# Alimentation.net
KiCad netlist of a schematic drawn in Altium Designer
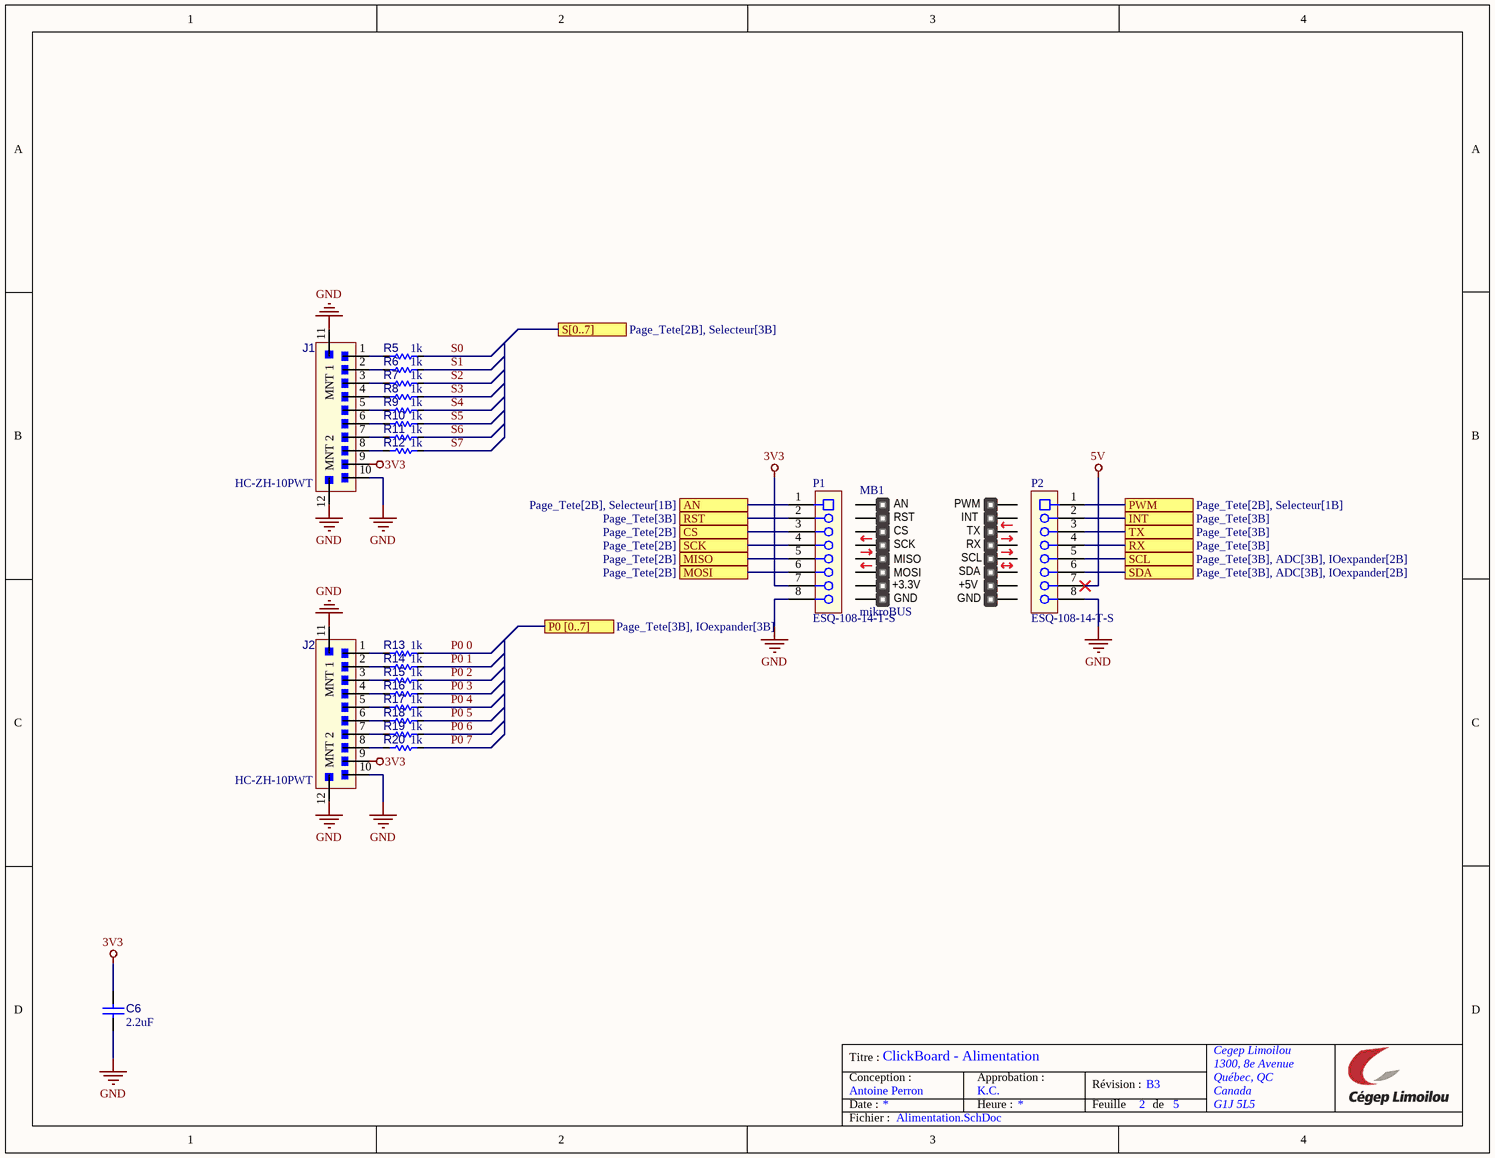
[diagram p0: Alimentation.SchDoc]

(export (version "E")
  (design (tool "Eeschema 10.0.6"))
  (components
    (comp (ref "C6")
      (value "2.2uF")
      (footprint "C_1608[0603]")
      (description "Capacitor type 1")
      (fields (field (name "TOLERANCE") "10%") (field (name "Comment") "CAP CER 2.2uF 10V X7R 0603"))
      (libsource (lib "TEP-AltiumLib-Passives-RLC") (part "capacitor"))
    )
    (comp (ref "J1")
      (value "HC-ZH-10PWT")
      (footprint "J_S10B-ZR-SM4")
      (description "CONN wire to board SMT R/A 10POS 1.5mm")
      (libsource (lib "TEP-AltiumLib-Connectors") (part "CONN-1MM5-01X10-S10B-H-SMT"))
    )
    (comp (ref "J2")
      (value "HC-ZH-10PWT")
      (footprint "J_S10B-ZR-SM4")
      (description "CONN wire to board SMT R/A 10POS 1.5mm")
      (libsource (lib "TEP-AltiumLib-Connectors") (part "CONN-1MM5-01X10-S10B-H-SMT"))
    )
    (comp (ref "MB1")
      (value "mikroBUS")
      (footprint "mikroBUS-Large-No-Connector")
      (description "mikroBUS compatible add-on board")
      (libsource (lib "TEP-AltiumLib-Modules") (part "mikroBUS compatible add-on board"))
    )
    (comp (ref "P1")
      (value "ESQ-108-14-T-S")
      (footprint "CONN_SKT_01X08_100MIL-ELEVATED-LONGPIN")
      (description "CONN SOCKET 8pos 100mils Elevated")
      (libsource (lib "TEP-AltiumLib-Connectors") (part "CONN-100MIL-SKT-01X08_ELEVATED_LONGPIN"))
    )
    (comp (ref "P2")
      (value "ESQ-108-14-T-S")
      (footprint "CONN_SKT_01X08_100MIL-ELEVATED-LONGPIN")
      (description "CONN SOCKET 8pos 100mils Elevated")
      (libsource (lib "") (part "CONN-100MIL-SKT-01X08_ELEVATED_LONGPIN_1"))
    )
    (comp (ref "R5")
      (value "1k")
      (footprint "R_1608[0603]")
      (description "Resistor type 1")
      (fields (field (name "TOLERANCE") "1%") (field (name "Comment") "Res 1k 1% 0603"))
      (libsource (lib "TEP-AltiumLib-Passives-RLC") (part "resistor"))
    )
    (comp (ref "R6")
      (value "1k")
      (footprint "R_1608[0603]")
      (description "Resistor type 1")
      (fields (field (name "TOLERANCE") "1%") (field (name "Comment") "Res 1k 1% 0603"))
      (libsource (lib "TEP-AltiumLib-Passives-RLC") (part "resistor"))
    )
    (comp (ref "R7")
      (value "1k")
      (footprint "R_1608[0603]")
      (description "Resistor type 1")
      (fields (field (name "TOLERANCE") "1%") (field (name "Comment") "Res 1k 1% 0603"))
      (libsource (lib "TEP-AltiumLib-Passives-RLC") (part "resistor"))
    )
    (comp (ref "R8")
      (value "1k")
      (footprint "R_1608[0603]")
      (description "Resistor type 1")
      (fields (field (name "TOLERANCE") "1%") (field (name "Comment") "Res 1k 1% 0603"))
      (libsource (lib "TEP-AltiumLib-Passives-RLC") (part "resistor"))
    )
    (comp (ref "R9")
      (value "1k")
      (footprint "R_1608[0603]")
      (description "Resistor type 1")
      (fields (field (name "TOLERANCE") "1%") (field (name "Comment") "Res 1k 1% 0603"))
      (libsource (lib "TEP-AltiumLib-Passives-RLC") (part "resistor"))
    )
    (comp (ref "R10")
      (value "1k")
      (footprint "R_1608[0603]")
      (description "Resistor type 1")
      (fields (field (name "TOLERANCE") "1%") (field (name "Comment") "Res 1k 1% 0603"))
      (libsource (lib "TEP-AltiumLib-Passives-RLC") (part "resistor"))
    )
    (comp (ref "R11")
      (value "1k")
      (footprint "R_1608[0603]")
      (description "Resistor type 1")
      (fields (field (name "TOLERANCE") "1%") (field (name "Comment") "Res 1k 1% 0603"))
      (libsource (lib "TEP-AltiumLib-Passives-RLC") (part "resistor"))
    )
    (comp (ref "R12")
      (value "1k")
      (footprint "R_1608[0603]")
      (description "Resistor type 1")
      (fields (field (name "TOLERANCE") "1%") (field (name "Comment") "Res 1k 1% 0603"))
      (libsource (lib "TEP-AltiumLib-Passives-RLC") (part "resistor"))
    )
    (comp (ref "R13")
      (value "1k")
      (footprint "R_1608[0603]")
      (description "Resistor type 1")
      (fields (field (name "TOLERANCE") "1%") (field (name "Comment") "Res 1k 1% 0603"))
      (libsource (lib "TEP-AltiumLib-Passives-RLC") (part "resistor"))
    )
    (comp (ref "R14")
      (value "1k")
      (footprint "R_1608[0603]")
      (description "Resistor type 1")
      (fields (field (name "TOLERANCE") "1%") (field (name "Comment") "Res 1k 1% 0603"))
      (libsource (lib "TEP-AltiumLib-Passives-RLC") (part "resistor"))
    )
    (comp (ref "R15")
      (value "1k")
      (footprint "R_1608[0603]")
      (description "Resistor type 1")
      (fields (field (name "TOLERANCE") "1%") (field (name "Comment") "Res 1k 1% 0603"))
      (libsource (lib "TEP-AltiumLib-Passives-RLC") (part "resistor"))
    )
    (comp (ref "R16")
      (value "1k")
      (footprint "R_1608[0603]")
      (description "Resistor type 1")
      (fields (field (name "TOLERANCE") "1%") (field (name "Comment") "Res 1k 1% 0603"))
      (libsource (lib "TEP-AltiumLib-Passives-RLC") (part "resistor"))
    )
    (comp (ref "R17")
      (value "1k")
      (footprint "R_1608[0603]")
      (description "Resistor type 1")
      (fields (field (name "TOLERANCE") "1%") (field (name "Comment") "Res 1k 1% 0603"))
      (libsource (lib "TEP-AltiumLib-Passives-RLC") (part "resistor"))
    )
    (comp (ref "R18")
      (value "1k")
      (footprint "R_1608[0603]")
      (description "Resistor type 1")
      (fields (field (name "TOLERANCE") "1%") (field (name "Comment") "Res 1k 1% 0603"))
      (libsource (lib "TEP-AltiumLib-Passives-RLC") (part "resistor"))
    )
    (comp (ref "R19")
      (value "1k")
      (footprint "R_1608[0603]")
      (description "Resistor type 1")
      (fields (field (name "TOLERANCE") "1%") (field (name "Comment") "Res 1k 1% 0603"))
      (libsource (lib "TEP-AltiumLib-Passives-RLC") (part "resistor"))
    )
    (comp (ref "R20")
      (value "1k")
      (footprint "R_1608[0603]")
      (description "Resistor type 1")
      (fields (field (name "TOLERANCE") "1%") (field (name "Comment") "Res 1k 1% 0603"))
      (libsource (lib "TEP-AltiumLib-Passives-RLC") (part "resistor"))
    )
  )
  (nets
    (net (code "1") (name "/AN") (class "Default")
      (node (ref "P1") (pin "1") (pinfunction "1_1") (pintype "passive"))
    )
    (net (code "2") (name "/CS") (class "Default")
      (node (ref "P1") (pin "3") (pinfunction "3_3") (pintype "passive"))
    )
    (net (code "3") (name "/INT") (class "Default")
      (node (ref "P2") (pin "2") (pinfunction "2_2") (pintype "passive"))
    )
    (net (code "4") (name "/MISO") (class "Default")
      (node (ref "P1") (pin "5") (pinfunction "5_5") (pintype "passive"))
    )
    (net (code "5") (name "/MOSI") (class "Default")
      (node (ref "P1") (pin "6") (pinfunction "6_6") (pintype "passive"))
    )
    (net (code "6") (name "/P0 0") (class "Default")
      (node (ref "R13") (pin "2") (pinfunction "2_2") (pintype "passive"))
    )
    (net (code "7") (name "/P0 1") (class "Default")
      (node (ref "R14") (pin "2") (pinfunction "2_2") (pintype "passive"))
    )
    (net (code "8") (name "/P0 2") (class "Default")
      (node (ref "R15") (pin "2") (pinfunction "2_2") (pintype "passive"))
    )
    (net (code "9") (name "/P0 3") (class "Default")
      (node (ref "R16") (pin "2") (pinfunction "2_2") (pintype "passive"))
    )
    (net (code "10") (name "/P0 4") (class "Default")
      (node (ref "R17") (pin "2") (pinfunction "2_2") (pintype "passive"))
    )
    (net (code "11") (name "/P0 5") (class "Default")
      (node (ref "R18") (pin "2") (pinfunction "2_2") (pintype "passive"))
    )
    (net (code "12") (name "/P0 6") (class "Default")
      (node (ref "R19") (pin "2") (pinfunction "2_2") (pintype "passive"))
    )
    (net (code "13") (name "/P0 7") (class "Default")
      (node (ref "R20") (pin "2") (pinfunction "2_2") (pintype "passive"))
    )
    (net (code "15") (name "/PWM") (class "Default")
      (node (ref "P2") (pin "1") (pinfunction "1_1") (pintype "passive"))
    )
    (net (code "16") (name "/RST") (class "Default")
      (node (ref "P1") (pin "2") (pinfunction "2_2") (pintype "passive"))
    )
    (net (code "17") (name "/RX") (class "Default")
      (node (ref "P2") (pin "4") (pinfunction "4_4") (pintype "passive"))
    )
    (net (code "18") (name "/S0") (class "Default")
      (node (ref "R5") (pin "2") (pinfunction "2_2") (pintype "passive"))
    )
    (net (code "19") (name "/S1") (class "Default")
      (node (ref "R6") (pin "2") (pinfunction "2_2") (pintype "passive"))
    )
    (net (code "20") (name "/S2") (class "Default")
      (node (ref "R7") (pin "2") (pinfunction "2_2") (pintype "passive"))
    )
    (net (code "21") (name "/S3") (class "Default")
      (node (ref "R8") (pin "2") (pinfunction "2_2") (pintype "passive"))
    )
    (net (code "22") (name "/S4") (class "Default")
      (node (ref "R9") (pin "2") (pinfunction "2_2") (pintype "passive"))
    )
    (net (code "23") (name "/S5") (class "Default")
      (node (ref "R10") (pin "2") (pinfunction "2_2") (pintype "passive"))
    )
    (net (code "24") (name "/S6") (class "Default")
      (node (ref "R11") (pin "2") (pinfunction "2_2") (pintype "passive"))
    )
    (net (code "25") (name "/S7") (class "Default")
      (node (ref "R12") (pin "2") (pinfunction "2_2") (pintype "passive"))
    )
    (net (code "26") (name "/SCK") (class "Default")
      (node (ref "P1") (pin "4") (pinfunction "4_4") (pintype "passive"))
    )
    (net (code "27") (name "/SCL") (class "Default")
      (node (ref "P2") (pin "5") (pinfunction "5_5") (pintype "passive"))
    )
    (net (code "28") (name "/SDA") (class "Default")
      (node (ref "P2") (pin "6") (pinfunction "6_6") (pintype "passive"))
    )
    (net (code "30") (name "/TX") (class "Default")
      (node (ref "P2") (pin "3") (pinfunction "3_3") (pintype "passive"))
    )
    (net (code "31") (name "3V3") (class "Default")
      (node (ref "C6") (pin "2") (pinfunction "2_2") (pintype "passive"))
      (node (ref "J1") (pin "9") (pinfunction "9_9") (pintype "passive"))
      (node (ref "J2") (pin "9") (pinfunction "9_9") (pintype "passive"))
      (node (ref "P1") (pin "7") (pinfunction "7_7") (pintype "passive"))
    )
    (net (code "32") (name "5V") (class "Default")
      (node (ref "P2") (pin "7") (pinfunction "7_7") (pintype "passive"))
    )
    (net (code "33") (name "GND") (class "Default")
      (node (ref "C6") (pin "1") (pinfunction "1_1") (pintype "passive"))
      (node (ref "J1") (pin "10") (pinfunction "10_10") (pintype "passive"))
      (node (ref "J1") (pin "11") (pinfunction "MNT_1_11") (pintype "passive"))
      (node (ref "J1") (pin "12") (pinfunction "MNT_2_12") (pintype "passive"))
      (node (ref "J2") (pin "10") (pinfunction "10_10") (pintype "passive"))
      (node (ref "J2") (pin "11") (pinfunction "MNT_1_11") (pintype "passive"))
      (node (ref "J2") (pin "12") (pinfunction "MNT_2_12") (pintype "passive"))
      (node (ref "P1") (pin "8") (pinfunction "8_8") (pintype "passive"))
      (node (ref "P2") (pin "8") (pinfunction "8_8") (pintype "passive"))
    )
    (net (code "34") (name "Net-(J1-Pad1)") (class "Default")
      (node (ref "J1") (pin "1") (pinfunction "1_1") (pintype "passive"))
      (node (ref "R5") (pin "1") (pinfunction "1_1") (pintype "passive"))
    )
    (net (code "35") (name "Net-(J1-Pad2)") (class "Default")
      (node (ref "J1") (pin "2") (pinfunction "2_2") (pintype "passive"))
      (node (ref "R6") (pin "1") (pinfunction "1_1") (pintype "passive"))
    )
    (net (code "36") (name "Net-(J1-Pad3)") (class "Default")
      (node (ref "J1") (pin "3") (pinfunction "3_3") (pintype "passive"))
      (node (ref "R7") (pin "1") (pinfunction "1_1") (pintype "passive"))
    )
    (net (code "37") (name "Net-(J1-Pad4)") (class "Default")
      (node (ref "J1") (pin "4") (pinfunction "4_4") (pintype "passive"))
      (node (ref "R8") (pin "1") (pinfunction "1_1") (pintype "passive"))
    )
    (net (code "38") (name "Net-(J1-Pad5)") (class "Default")
      (node (ref "J1") (pin "5") (pinfunction "5_5") (pintype "passive"))
      (node (ref "R9") (pin "1") (pinfunction "1_1") (pintype "passive"))
    )
    (net (code "39") (name "Net-(J1-Pad6)") (class "Default")
      (node (ref "J1") (pin "6") (pinfunction "6_6") (pintype "passive"))
      (node (ref "R10") (pin "1") (pinfunction "1_1") (pintype "passive"))
    )
    (net (code "40") (name "Net-(J1-Pad7)") (class "Default")
      (node (ref "J1") (pin "7") (pinfunction "7_7") (pintype "passive"))
      (node (ref "R11") (pin "1") (pinfunction "1_1") (pintype "passive"))
    )
    (net (code "41") (name "Net-(J1-Pad8)") (class "Default")
      (node (ref "J1") (pin "8") (pinfunction "8_8") (pintype "passive"))
      (node (ref "R12") (pin "1") (pinfunction "1_1") (pintype "passive"))
    )
    (net (code "42") (name "Net-(J2-Pad1)") (class "Default")
      (node (ref "J2") (pin "1") (pinfunction "1_1") (pintype "passive"))
      (node (ref "R13") (pin "1") (pinfunction "1_1") (pintype "passive"))
    )
    (net (code "43") (name "Net-(J2-Pad2)") (class "Default")
      (node (ref "J2") (pin "2") (pinfunction "2_2") (pintype "passive"))
      (node (ref "R14") (pin "1") (pinfunction "1_1") (pintype "passive"))
    )
    (net (code "44") (name "Net-(J2-Pad3)") (class "Default")
      (node (ref "J2") (pin "3") (pinfunction "3_3") (pintype "passive"))
      (node (ref "R15") (pin "1") (pinfunction "1_1") (pintype "passive"))
    )
    (net (code "45") (name "Net-(J2-Pad4)") (class "Default")
      (node (ref "J2") (pin "4") (pinfunction "4_4") (pintype "passive"))
      (node (ref "R16") (pin "1") (pinfunction "1_1") (pintype "passive"))
    )
    (net (code "46") (name "Net-(J2-Pad5)") (class "Default")
      (node (ref "J2") (pin "5") (pinfunction "5_5") (pintype "passive"))
      (node (ref "R17") (pin "1") (pinfunction "1_1") (pintype "passive"))
    )
    (net (code "47") (name "Net-(J2-Pad6)") (class "Default")
      (node (ref "J2") (pin "6") (pinfunction "6_6") (pintype "passive"))
      (node (ref "R18") (pin "1") (pinfunction "1_1") (pintype "passive"))
    )
    (net (code "48") (name "Net-(J2-Pad7)") (class "Default")
      (node (ref "J2") (pin "7") (pinfunction "7_7") (pintype "passive"))
      (node (ref "R19") (pin "1") (pinfunction "1_1") (pintype "passive"))
    )
    (net (code "49") (name "Net-(J2-Pad8)") (class "Default")
      (node (ref "J2") (pin "8") (pinfunction "8_8") (pintype "passive"))
      (node (ref "R20") (pin "1") (pinfunction "1_1") (pintype "passive"))
    )
    (net (code "50") (name "unconnected-(MB1-3.3V-Pad7)") (class "Default")
      (node (ref "MB1") (pin "7") (pinfunction "3.3V_7") (pintype "passive"))
    )
    (net (code "51") (name "unconnected-(MB1-5V-Pad10)") (class "Default")
      (node (ref "MB1") (pin "10") (pinfunction "5V_10") (pintype "passive"))
    )
    (net (code "52") (name "unconnected-(MB1-AN-Pad1)") (class "Default")
      (node (ref "MB1") (pin "1") (pinfunction "AN_1") (pintype "passive"))
    )
    (net (code "53") (name "unconnected-(MB1-CS-Pad3)") (class "Default")
      (node (ref "MB1") (pin "3") (pinfunction "CS_3") (pintype "passive"))
    )
    (net (code "54") (name "unconnected-(MB1-GND-Pad8)") (class "Default")
      (node (ref "MB1") (pin "8") (pinfunction "GND_8") (pintype "passive"))
    )
    (net (code "55") (name "unconnected-(MB1-GND-Pad9)") (class "Default")
      (node (ref "MB1") (pin "9") (pinfunction "GND_9") (pintype "passive"))
    )
    (net (code "56") (name "unconnected-(MB1-INT-Pad15)") (class "Default")
      (node (ref "MB1") (pin "15") (pinfunction "INT_15") (pintype "passive"))
    )
    (net (code "57") (name "unconnected-(MB1-MISO-Pad5)") (class "Default")
      (node (ref "MB1") (pin "5") (pinfunction "MISO_5") (pintype "passive"))
    )
    (net (code "58") (name "unconnected-(MB1-MOSI-Pad6)") (class "Default")
      (node (ref "MB1") (pin "6") (pinfunction "MOSI_6") (pintype "passive"))
    )
    (net (code "59") (name "unconnected-(MB1-PWM-Pad16)") (class "Default")
      (node (ref "MB1") (pin "16") (pinfunction "PWM_16") (pintype "passive"))
    )
    (net (code "60") (name "unconnected-(MB1-RST-Pad2)") (class "Default")
      (node (ref "MB1") (pin "2") (pinfunction "RST_2") (pintype "passive"))
    )
    (net (code "61") (name "unconnected-(MB1-RX-Pad14)") (class "Default")
      (node (ref "MB1") (pin "14") (pinfunction "RX_14") (pintype "passive"))
    )
    (net (code "62") (name "unconnected-(MB1-SCK-Pad4)") (class "Default")
      (node (ref "MB1") (pin "4") (pinfunction "SCK_4") (pintype "passive"))
    )
    (net (code "63") (name "unconnected-(MB1-SCL-Pad12)") (class "Default")
      (node (ref "MB1") (pin "12") (pinfunction "SCL_12") (pintype "passive"))
    )
    (net (code "64") (name "unconnected-(MB1-SDA-Pad11)") (class "Default")
      (node (ref "MB1") (pin "11") (pinfunction "SDA_11") (pintype "passive"))
    )
    (net (code "65") (name "unconnected-(MB1-TX-Pad13)") (class "Default")
      (node (ref "MB1") (pin "13") (pinfunction "TX_13") (pintype "passive"))
    )
  )
)
